# Sheet1.net
KiCad netlist of a schematic drawn in Altium Designer
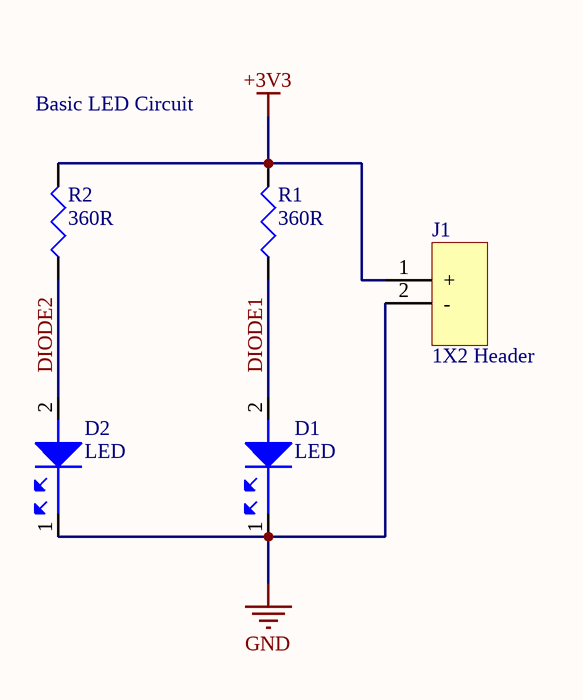
[diagram p0: Sheet1.SchDoc]

(export (version "E")
  (design (tool "Eeschema 10.0.6"))
  (components
    (comp (ref "D1")
      (value "LED")
      (footprint "LED0603G")
      (description "SC, VISIBLE LED SMD-Thin USS,InGaAlP,Hi Brt Orange")
      (libsource (lib "Schlib1") (part "LNJ826W83RA"))
    )
    (comp (ref "D2")
      (value "LED")
      (footprint "LED0603G")
      (description "SC, VISIBLE LED SMD-Thin USS,InGaAlP,Hi Brt Orange")
      (libsource (lib "Schlib1") (part "LNJ826W83RA"))
    )
    (comp (ref "J1")
      (value "1X2 Header")
      (footprint "HDR1X2")
      (description "CONN HEADER VERT 2POS 2.54MM")
      (libsource (lib "Schlib1") (part "22-29-2021"))
    )
    (comp (ref "R1")
      (value "360R")
      (footprint "R0805")
      (description "RES SMD 360 OHM 1% 1/2W 0805")
      (fields (field (name "TOLERANCE") "1%"))
      (libsource (lib "Schlib1") (part "CRCW0805360RFKEAHP"))
    )
    (comp (ref "R2")
      (value "360R")
      (footprint "R0805")
      (description "RES SMD 360 OHM 1% 1/2W 0805")
      (fields (field (name "TOLERANCE") "1%"))
      (libsource (lib "Schlib1") (part "CRCW0805360RFKEAHP"))
    )
  )
  (nets
    (net (code "1") (name "+3V3") (class "Default")
      (node (ref "J1") (pin "1") (pinfunction "+_1") (pintype "passive"))
      (node (ref "R1") (pin "2") (pinfunction "2_2") (pintype "passive"))
      (node (ref "R2") (pin "2") (pinfunction "2_2") (pintype "passive"))
    )
    (net (code "2") (name "/DIODE1") (class "Default")
      (node (ref "D1") (pin "2") (pinfunction "2_2") (pintype "passive"))
      (node (ref "R1") (pin "1") (pinfunction "1_1") (pintype "passive"))
    )
    (net (code "3") (name "/DIODE2") (class "Default")
      (node (ref "D2") (pin "2") (pinfunction "2_2") (pintype "passive"))
      (node (ref "R2") (pin "1") (pinfunction "1_1") (pintype "passive"))
    )
    (net (code "4") (name "GND") (class "Default")
      (node (ref "D1") (pin "1") (pinfunction "1_1") (pintype "passive"))
      (node (ref "D2") (pin "1") (pinfunction "1_1") (pintype "passive"))
      (node (ref "J1") (pin "2") (pinfunction "-_2") (pintype "passive"))
    )
  )
)
